# headstage.net
KiCad netlist of a schematic drawn in EAGLE
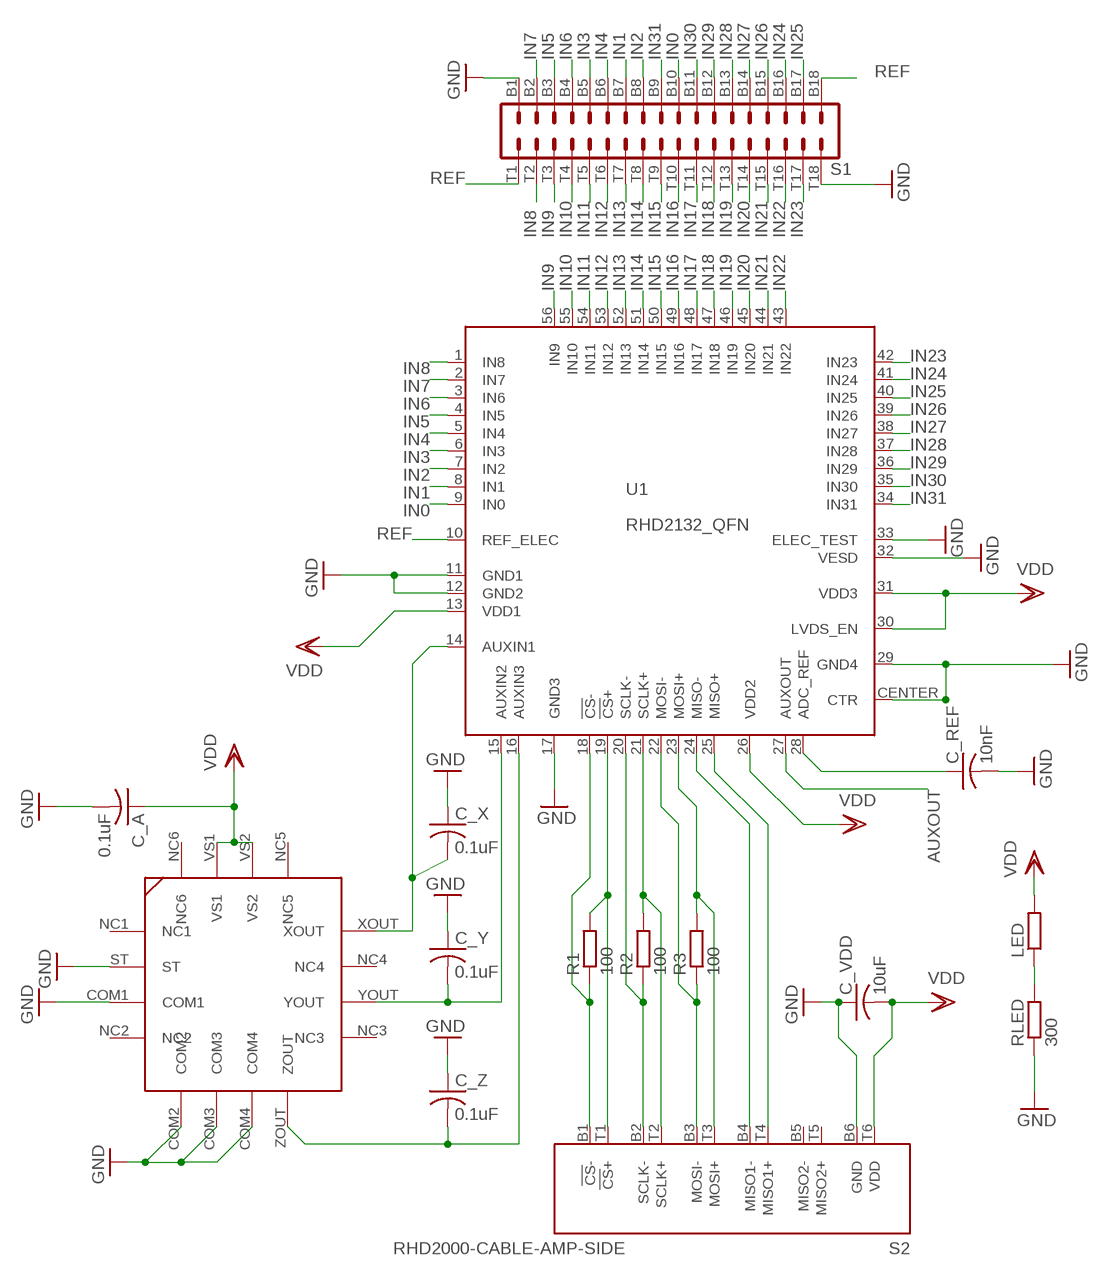
[diagram p0: schematic, sheet 1]

(export (version "E")
  (design (tool "Eeschema 10.0.6"))
  (components
    (comp (ref "C_A")
      (value "0.1uF")
      (footprint "eagle-import:C0402K")
      (libsource (lib "eagle-import") (part "C-USC0402K"))
    )
    (comp (ref "C_REF")
      (value "10nF")
      (footprint "eagle-import:C0402K")
      (libsource (lib "eagle-import") (part "C-USC0402K"))
    )
    (comp (ref "C_VDD")
      (value "10uF")
      (footprint "eagle-import:C0402K")
      (libsource (lib "eagle-import") (part "C-USC0402K"))
    )
    (comp (ref "C_X")
      (value "0.1uF")
      (footprint "eagle-import:C0402K")
      (libsource (lib "eagle-import") (part "C-USC0402K"))
    )
    (comp (ref "C_Y")
      (value "0.1uF")
      (footprint "eagle-import:C0402K")
      (libsource (lib "eagle-import") (part "C-USC0402K"))
    )
    (comp (ref "C_Z")
      (value "0.1uF")
      (footprint "eagle-import:C0402K")
      (libsource (lib "eagle-import") (part "C-USC0402K"))
    )
    (comp (ref "LED")
      (value "R-EU_R0402")
      (footprint "eagle-import:R0402")
      (libsource (lib "eagle-import") (part "R-EU_R0402"))
    )
    (comp (ref "R1")
      (value "100")
      (footprint "eagle-import:R0402")
      (libsource (lib "eagle-import") (part "R-EU_R0402"))
    )
    (comp (ref "R2")
      (value "100")
      (footprint "eagle-import:R0402")
      (libsource (lib "eagle-import") (part "R-EU_R0402"))
    )
    (comp (ref "R3")
      (value "100")
      (footprint "eagle-import:R0402")
      (libsource (lib "eagle-import") (part "R-EU_R0402"))
    )
    (comp (ref "RLED")
      (value "300")
      (footprint "eagle-import:R0402")
      (libsource (lib "eagle-import") (part "R-EU_R0402"))
    )
    (comp (ref "S1")
      (value "OMNETICS_A79025")
      (footprint "eagle-import:OMNETICS_A79025")
      (libsource (lib "eagle-import") (part "OMNETICS_A79025"))
    )
    (comp (ref "S2")
      (value "RHD2000-CABLE-AMP-SIDE")
      (footprint "eagle-import:OMNETICS_PZN-12-AA")
      (libsource (lib "eagle-import") (part "RHD2000-CABLE-AMP-SIDE"))
    )
    (comp (ref "U$1")
      (value "ADXL335")
      (footprint "eagle-import:ADXL335")
      (libsource (lib "eagle-import") (part "ADXL335"))
    )
    (comp (ref "U1")
      (value "RHD2132_QFN")
      (footprint "eagle-import:QFN56_8_X_8_LARGE")
      (libsource (lib "eagle-import") (part "RHD2132_QFN"))
    )
  )
  (nets
    (net (code "1") (name "/AUXOUT") (class "Default")
      (node (ref "U1") (pin "27") (pinfunction "AUXOUT_27") (pintype "tri_state"))
    )
    (net (code "2") (name "/IN0") (class "Default")
      (node (ref "S1") (pin "B10") (pinfunction "B10_B10") (pintype "passive"))
      (node (ref "U1") (pin "9") (pinfunction "IN0_9") (pintype "input"))
    )
    (net (code "3") (name "/IN1") (class "Default")
      (node (ref "S1") (pin "B7") (pinfunction "B7_B7") (pintype "passive"))
      (node (ref "U1") (pin "8") (pinfunction "IN1_8") (pintype "input"))
    )
    (net (code "4") (name "/IN2") (class "Default")
      (node (ref "S1") (pin "B8") (pinfunction "B8_B8") (pintype "passive"))
      (node (ref "U1") (pin "7") (pinfunction "IN2_7") (pintype "input"))
    )
    (net (code "5") (name "/IN3") (class "Default")
      (node (ref "S1") (pin "B5") (pinfunction "B5_B5") (pintype "passive"))
      (node (ref "U1") (pin "6") (pinfunction "IN3_6") (pintype "input"))
    )
    (net (code "6") (name "/IN4") (class "Default")
      (node (ref "S1") (pin "B6") (pinfunction "B6_B6") (pintype "passive"))
      (node (ref "U1") (pin "5") (pinfunction "IN4_5") (pintype "input"))
    )
    (net (code "7") (name "/IN5") (class "Default")
      (node (ref "S1") (pin "B3") (pinfunction "B3_B3") (pintype "passive"))
      (node (ref "U1") (pin "4") (pinfunction "IN5_4") (pintype "input"))
    )
    (net (code "8") (name "/IN6") (class "Default")
      (node (ref "S1") (pin "B4") (pinfunction "B4_B4") (pintype "passive"))
      (node (ref "U1") (pin "3") (pinfunction "IN6_3") (pintype "input"))
    )
    (net (code "9") (name "/IN7") (class "Default")
      (node (ref "S1") (pin "B2") (pinfunction "B2_B2") (pintype "passive"))
      (node (ref "U1") (pin "2") (pinfunction "IN7_2") (pintype "input"))
    )
    (net (code "10") (name "/IN8") (class "Default")
      (node (ref "S1") (pin "T2") (pinfunction "T2_T2") (pintype "passive"))
      (node (ref "U1") (pin "1") (pinfunction "IN8_1") (pintype "input"))
    )
    (net (code "11") (name "/IN9") (class "Default")
      (node (ref "S1") (pin "T3") (pinfunction "T3_T3") (pintype "passive"))
      (node (ref "U1") (pin "56") (pinfunction "IN9_56") (pintype "input"))
    )
    (net (code "12") (name "/IN10") (class "Default")
      (node (ref "S1") (pin "T4") (pinfunction "T4_T4") (pintype "passive"))
      (node (ref "U1") (pin "55") (pinfunction "IN10_55") (pintype "input"))
    )
    (net (code "13") (name "/IN11") (class "Default")
      (node (ref "S1") (pin "T5") (pinfunction "T5_T5") (pintype "passive"))
      (node (ref "U1") (pin "54") (pinfunction "IN11_54") (pintype "input"))
    )
    (net (code "14") (name "/IN12") (class "Default")
      (node (ref "S1") (pin "T6") (pinfunction "T6_T6") (pintype "passive"))
      (node (ref "U1") (pin "53") (pinfunction "IN12_53") (pintype "input"))
    )
    (net (code "15") (name "/IN13") (class "Default")
      (node (ref "S1") (pin "T7") (pinfunction "T7_T7") (pintype "passive"))
      (node (ref "U1") (pin "52") (pinfunction "IN13_52") (pintype "input"))
    )
    (net (code "16") (name "/IN14") (class "Default")
      (node (ref "S1") (pin "T8") (pinfunction "T8_T8") (pintype "passive"))
      (node (ref "U1") (pin "51") (pinfunction "IN14_51") (pintype "input"))
    )
    (net (code "17") (name "/IN15") (class "Default")
      (node (ref "S1") (pin "T9") (pinfunction "T9_T9") (pintype "passive"))
      (node (ref "U1") (pin "50") (pinfunction "IN15_50") (pintype "input"))
    )
    (net (code "18") (name "/IN16") (class "Default")
      (node (ref "S1") (pin "T10") (pinfunction "T10_T10") (pintype "passive"))
      (node (ref "U1") (pin "49") (pinfunction "IN16_49") (pintype "input"))
    )
    (net (code "19") (name "/IN17") (class "Default")
      (node (ref "S1") (pin "T11") (pinfunction "T11_T11") (pintype "passive"))
      (node (ref "U1") (pin "48") (pinfunction "IN17_48") (pintype "input"))
    )
    (net (code "20") (name "/IN18") (class "Default")
      (node (ref "S1") (pin "T12") (pinfunction "T12_T12") (pintype "passive"))
      (node (ref "U1") (pin "47") (pinfunction "IN18_47") (pintype "input"))
    )
    (net (code "21") (name "/IN19") (class "Default")
      (node (ref "S1") (pin "T13") (pinfunction "T13_T13") (pintype "passive"))
      (node (ref "U1") (pin "46") (pinfunction "IN19_46") (pintype "input"))
    )
    (net (code "22") (name "/IN20") (class "Default")
      (node (ref "S1") (pin "T14") (pinfunction "T14_T14") (pintype "passive"))
      (node (ref "U1") (pin "45") (pinfunction "IN20_45") (pintype "input"))
    )
    (net (code "23") (name "/IN21") (class "Default")
      (node (ref "S1") (pin "T15") (pinfunction "T15_T15") (pintype "passive"))
      (node (ref "U1") (pin "44") (pinfunction "IN21_44") (pintype "input"))
    )
    (net (code "24") (name "/IN22") (class "Default")
      (node (ref "S1") (pin "T16") (pinfunction "T16_T16") (pintype "passive"))
      (node (ref "U1") (pin "43") (pinfunction "IN22_43") (pintype "input"))
    )
    (net (code "25") (name "/IN23") (class "Default")
      (node (ref "S1") (pin "T17") (pinfunction "T17_T17") (pintype "passive"))
      (node (ref "U1") (pin "42") (pinfunction "IN23_42") (pintype "input"))
    )
    (net (code "26") (name "/IN24") (class "Default")
      (node (ref "S1") (pin "B16") (pinfunction "B16_B16") (pintype "passive"))
      (node (ref "U1") (pin "41") (pinfunction "IN24_41") (pintype "input"))
    )
    (net (code "27") (name "/IN25") (class "Default")
      (node (ref "S1") (pin "B17") (pinfunction "B17_B17") (pintype "passive"))
      (node (ref "U1") (pin "40") (pinfunction "IN25_40") (pintype "input"))
    )
    (net (code "28") (name "/IN26") (class "Default")
      (node (ref "S1") (pin "B15") (pinfunction "B15_B15") (pintype "passive"))
      (node (ref "U1") (pin "39") (pinfunction "IN26_39") (pintype "input"))
    )
    (net (code "29") (name "/IN27") (class "Default")
      (node (ref "S1") (pin "B14") (pinfunction "B14_B14") (pintype "passive"))
      (node (ref "U1") (pin "38") (pinfunction "IN27_38") (pintype "input"))
    )
    (net (code "30") (name "/IN28") (class "Default")
      (node (ref "S1") (pin "B13") (pinfunction "B13_B13") (pintype "passive"))
      (node (ref "U1") (pin "37") (pinfunction "IN28_37") (pintype "input"))
    )
    (net (code "31") (name "/IN29") (class "Default")
      (node (ref "S1") (pin "B12") (pinfunction "B12_B12") (pintype "passive"))
      (node (ref "U1") (pin "36") (pinfunction "IN29_36") (pintype "input"))
    )
    (net (code "32") (name "/IN30") (class "Default")
      (node (ref "S1") (pin "B11") (pinfunction "B11_B11") (pintype "passive"))
      (node (ref "U1") (pin "35") (pinfunction "IN30_35") (pintype "input"))
    )
    (net (code "33") (name "/IN31") (class "Default")
      (node (ref "S1") (pin "B9") (pinfunction "B9_B9") (pintype "passive"))
      (node (ref "U1") (pin "34") (pinfunction "IN31_34") (pintype "input"))
    )
    (net (code "34") (name "/REF") (class "Default")
      (node (ref "S1") (pin "B18") (pinfunction "B18_B18") (pintype "passive"))
      (node (ref "S1") (pin "T1") (pinfunction "T1_T1") (pintype "passive"))
      (node (ref "U1") (pin "10") (pinfunction "REF_ELEC_10") (pintype "input"))
    )
    (net (code "35") (name "GND") (class "Default")
      (node (ref "C_A") (pin "2") (pinfunction "2_2") (pintype "passive"))
      (node (ref "C_REF") (pin "2") (pinfunction "2_2") (pintype "passive"))
      (node (ref "C_VDD") (pin "1") (pinfunction "1_1") (pintype "passive"))
      (node (ref "C_X") (pin "1") (pinfunction "1_1") (pintype "passive"))
      (node (ref "C_Y") (pin "1") (pinfunction "1_1") (pintype "passive"))
      (node (ref "C_Z") (pin "1") (pinfunction "1_1") (pintype "passive"))
      (node (ref "RLED") (pin "1") (pinfunction "1_1") (pintype "passive"))
      (node (ref "S1") (pin "B1") (pinfunction "B1_B1") (pintype "passive"))
      (node (ref "S1") (pin "T18") (pinfunction "T18_T18") (pintype "passive"))
      (node (ref "S2") (pin "B6") (pinfunction "GND_B6") (pintype "power_in"))
      (node (ref "U$1") (pin "COM1") (pinfunction "COM1_COM1") (pintype "bidirectional"))
      (node (ref "U$1") (pin "COM2") (pinfunction "COM2_COM2") (pintype "bidirectional"))
      (node (ref "U$1") (pin "COM3") (pinfunction "COM3_COM3") (pintype "bidirectional"))
      (node (ref "U$1") (pin "COM4") (pinfunction "COM4_COM4") (pintype "bidirectional"))
      (node (ref "U$1") (pin "ST") (pinfunction "ST_ST") (pintype "bidirectional"))
      (node (ref "U1") (pin "11") (pinfunction "GND1_11") (pintype "power_in"))
      (node (ref "U1") (pin "12") (pinfunction "GND2_12") (pintype "power_in"))
      (node (ref "U1") (pin "17") (pinfunction "GND3_17") (pintype "power_in"))
      (node (ref "U1") (pin "29") (pinfunction "GND4_29") (pintype "power_in"))
      (node (ref "U1") (pin "32") (pinfunction "VESD_32") (pintype "power_in"))
      (node (ref "U1") (pin "33") (pinfunction "ELEC_TEST_33") (pintype "input"))
      (node (ref "U1") (pin "CENTER") (pinfunction "CTR_CENTER") (pintype "power_in"))
    )
    (net (code "36") (name "Net-(LED-Pad1)") (class "Default")
      (node (ref "LED") (pin "1") (pinfunction "1_1") (pintype "passive"))
      (node (ref "RLED") (pin "2") (pinfunction "2_2") (pintype "passive"))
    )
    (net (code "37") (name "Net-(S2-MISO1+)") (class "Default")
      (node (ref "S2") (pin "T4") (pinfunction "MISO1+_T4") (pintype "bidirectional"))
      (node (ref "U1") (pin "25") (pinfunction "MISO+_25") (pintype "output"))
    )
    (net (code "38") (name "Net-(S2-MISO1-)") (class "Default")
      (node (ref "S2") (pin "B4") (pinfunction "MISO1-_B4") (pintype "bidirectional"))
      (node (ref "U1") (pin "24") (pinfunction "MISO-_24") (pintype "output"))
    )
    (net (code "39") (name "Net-(S2-MOSI+)") (class "Default")
      (node (ref "R3") (pin "2") (pinfunction "2_2") (pintype "passive"))
      (node (ref "S2") (pin "T3") (pinfunction "MOSI+_T3") (pintype "bidirectional"))
      (node (ref "U1") (pin "23") (pinfunction "MOSI+_23") (pintype "input"))
    )
    (net (code "40") (name "Net-(S2-MOSI-)") (class "Default")
      (node (ref "R3") (pin "1") (pinfunction "1_1") (pintype "passive"))
      (node (ref "S2") (pin "B3") (pinfunction "MOSI-_B3") (pintype "bidirectional"))
      (node (ref "U1") (pin "22") (pinfunction "MOSI-_22") (pintype "input"))
    )
    (net (code "41") (name "Net-(S2-SCLK+)") (class "Default")
      (node (ref "R2") (pin "2") (pinfunction "2_2") (pintype "passive"))
      (node (ref "S2") (pin "T2") (pinfunction "SCLK+_T2") (pintype "bidirectional"))
      (node (ref "U1") (pin "21") (pinfunction "SCLK+_21") (pintype "input"))
    )
    (net (code "42") (name "Net-(S2-SCLK-)") (class "Default")
      (node (ref "R2") (pin "1") (pinfunction "1_1") (pintype "passive"))
      (node (ref "S2") (pin "B2") (pinfunction "SCLK-_B2") (pintype "bidirectional"))
      (node (ref "U1") (pin "20") (pinfunction "SCLK-_20") (pintype "input"))
    )
    (net (code "43") (name "Net-(S2-~{CS}+)") (class "Default")
      (node (ref "R1") (pin "2") (pinfunction "2_2") (pintype "passive"))
      (node (ref "S2") (pin "T1") (pinfunction "~{CS}+_T1") (pintype "bidirectional"))
      (node (ref "U1") (pin "19") (pinfunction "~{CS}+_19") (pintype "input"))
    )
    (net (code "44") (name "Net-(S2-~{CS}-)") (class "Default")
      (node (ref "R1") (pin "1") (pinfunction "1_1") (pintype "passive"))
      (node (ref "S2") (pin "B1") (pinfunction "~{CS}-_B1") (pintype "bidirectional"))
      (node (ref "U1") (pin "18") (pinfunction "~{CS}-_18") (pintype "input"))
    )
    (net (code "45") (name "Net-(U1-ADC_REF)") (class "Default")
      (node (ref "C_REF") (pin "1") (pinfunction "1_1") (pintype "passive"))
      (node (ref "U1") (pin "28") (pinfunction "ADC_REF_28") (pintype "passive"))
    )
    (net (code "46") (name "Net-(U1-AUXIN1)") (class "Default")
      (node (ref "C_X") (pin "2") (pinfunction "2_2") (pintype "passive"))
      (node (ref "U$1") (pin "XOUT") (pinfunction "XOUT_XOUT") (pintype "bidirectional"))
      (node (ref "U1") (pin "14") (pinfunction "AUXIN1_14") (pintype "input"))
    )
    (net (code "47") (name "Net-(U1-AUXIN2)") (class "Default")
      (node (ref "C_Y") (pin "2") (pinfunction "2_2") (pintype "passive"))
      (node (ref "U$1") (pin "YOUT") (pinfunction "YOUT_YOUT") (pintype "bidirectional"))
      (node (ref "U1") (pin "15") (pinfunction "AUXIN2_15") (pintype "input"))
    )
    (net (code "48") (name "Net-(U1-AUXIN3)") (class "Default")
      (node (ref "C_Z") (pin "2") (pinfunction "2_2") (pintype "passive"))
      (node (ref "U$1") (pin "ZOUT") (pinfunction "ZOUT_ZOUT") (pintype "bidirectional"))
      (node (ref "U1") (pin "16") (pinfunction "AUXIN3_16") (pintype "input"))
    )
    (net (code "49") (name "VDD") (class "Default")
      (node (ref "C_A") (pin "1") (pinfunction "1_1") (pintype "passive"))
      (node (ref "C_VDD") (pin "2") (pinfunction "2_2") (pintype "passive"))
      (node (ref "LED") (pin "2") (pinfunction "2_2") (pintype "passive"))
      (node (ref "S2") (pin "T6") (pinfunction "VDD_T6") (pintype "bidirectional"))
      (node (ref "U$1") (pin "VS1") (pinfunction "VS1_VS1") (pintype "bidirectional"))
      (node (ref "U$1") (pin "VS2") (pinfunction "VS2_VS2") (pintype "bidirectional"))
      (node (ref "U1") (pin "13") (pinfunction "VDD1_13") (pintype "power_in"))
      (node (ref "U1") (pin "26") (pinfunction "VDD2_26") (pintype "power_in"))
      (node (ref "U1") (pin "30") (pinfunction "LVDS_EN_30") (pintype "input"))
      (node (ref "U1") (pin "31") (pinfunction "VDD3_31") (pintype "power_in"))
    )
    (net (code "50") (name "unconnected-(S2-MISO2+-PadT5)") (class "Default")
      (node (ref "S2") (pin "T5") (pinfunction "MISO2+_T5") (pintype "bidirectional"))
    )
    (net (code "51") (name "unconnected-(S2-MISO2--PadB5)") (class "Default")
      (node (ref "S2") (pin "B5") (pinfunction "MISO2-_B5") (pintype "bidirectional"))
    )
    (net (code "52") (name "unconnected-(U$1-PadNC1)") (class "Default")
      (node (ref "U$1") (pin "NC1") (pinfunction "NC1_NC1") (pintype "bidirectional"))
    )
    (net (code "53") (name "unconnected-(U$1-PadNC2)") (class "Default")
      (node (ref "U$1") (pin "NC2") (pinfunction "NC2_NC2") (pintype "bidirectional"))
    )
    (net (code "54") (name "unconnected-(U$1-PadNC3)") (class "Default")
      (node (ref "U$1") (pin "NC3") (pinfunction "NC3_NC3") (pintype "bidirectional"))
    )
    (net (code "55") (name "unconnected-(U$1-PadNC4)") (class "Default")
      (node (ref "U$1") (pin "NC4") (pinfunction "NC4_NC4") (pintype "bidirectional"))
    )
    (net (code "56") (name "unconnected-(U$1-PadNC5)") (class "Default")
      (node (ref "U$1") (pin "NC5") (pinfunction "NC5_NC5") (pintype "bidirectional"))
    )
    (net (code "57") (name "unconnected-(U$1-PadNC6)") (class "Default")
      (node (ref "U$1") (pin "NC6") (pinfunction "NC6_NC6") (pintype "bidirectional"))
    )
  )
)
